# SAMA7G54_DDR3L.net
KiCad netlist of a schematic drawn in Altium Designer
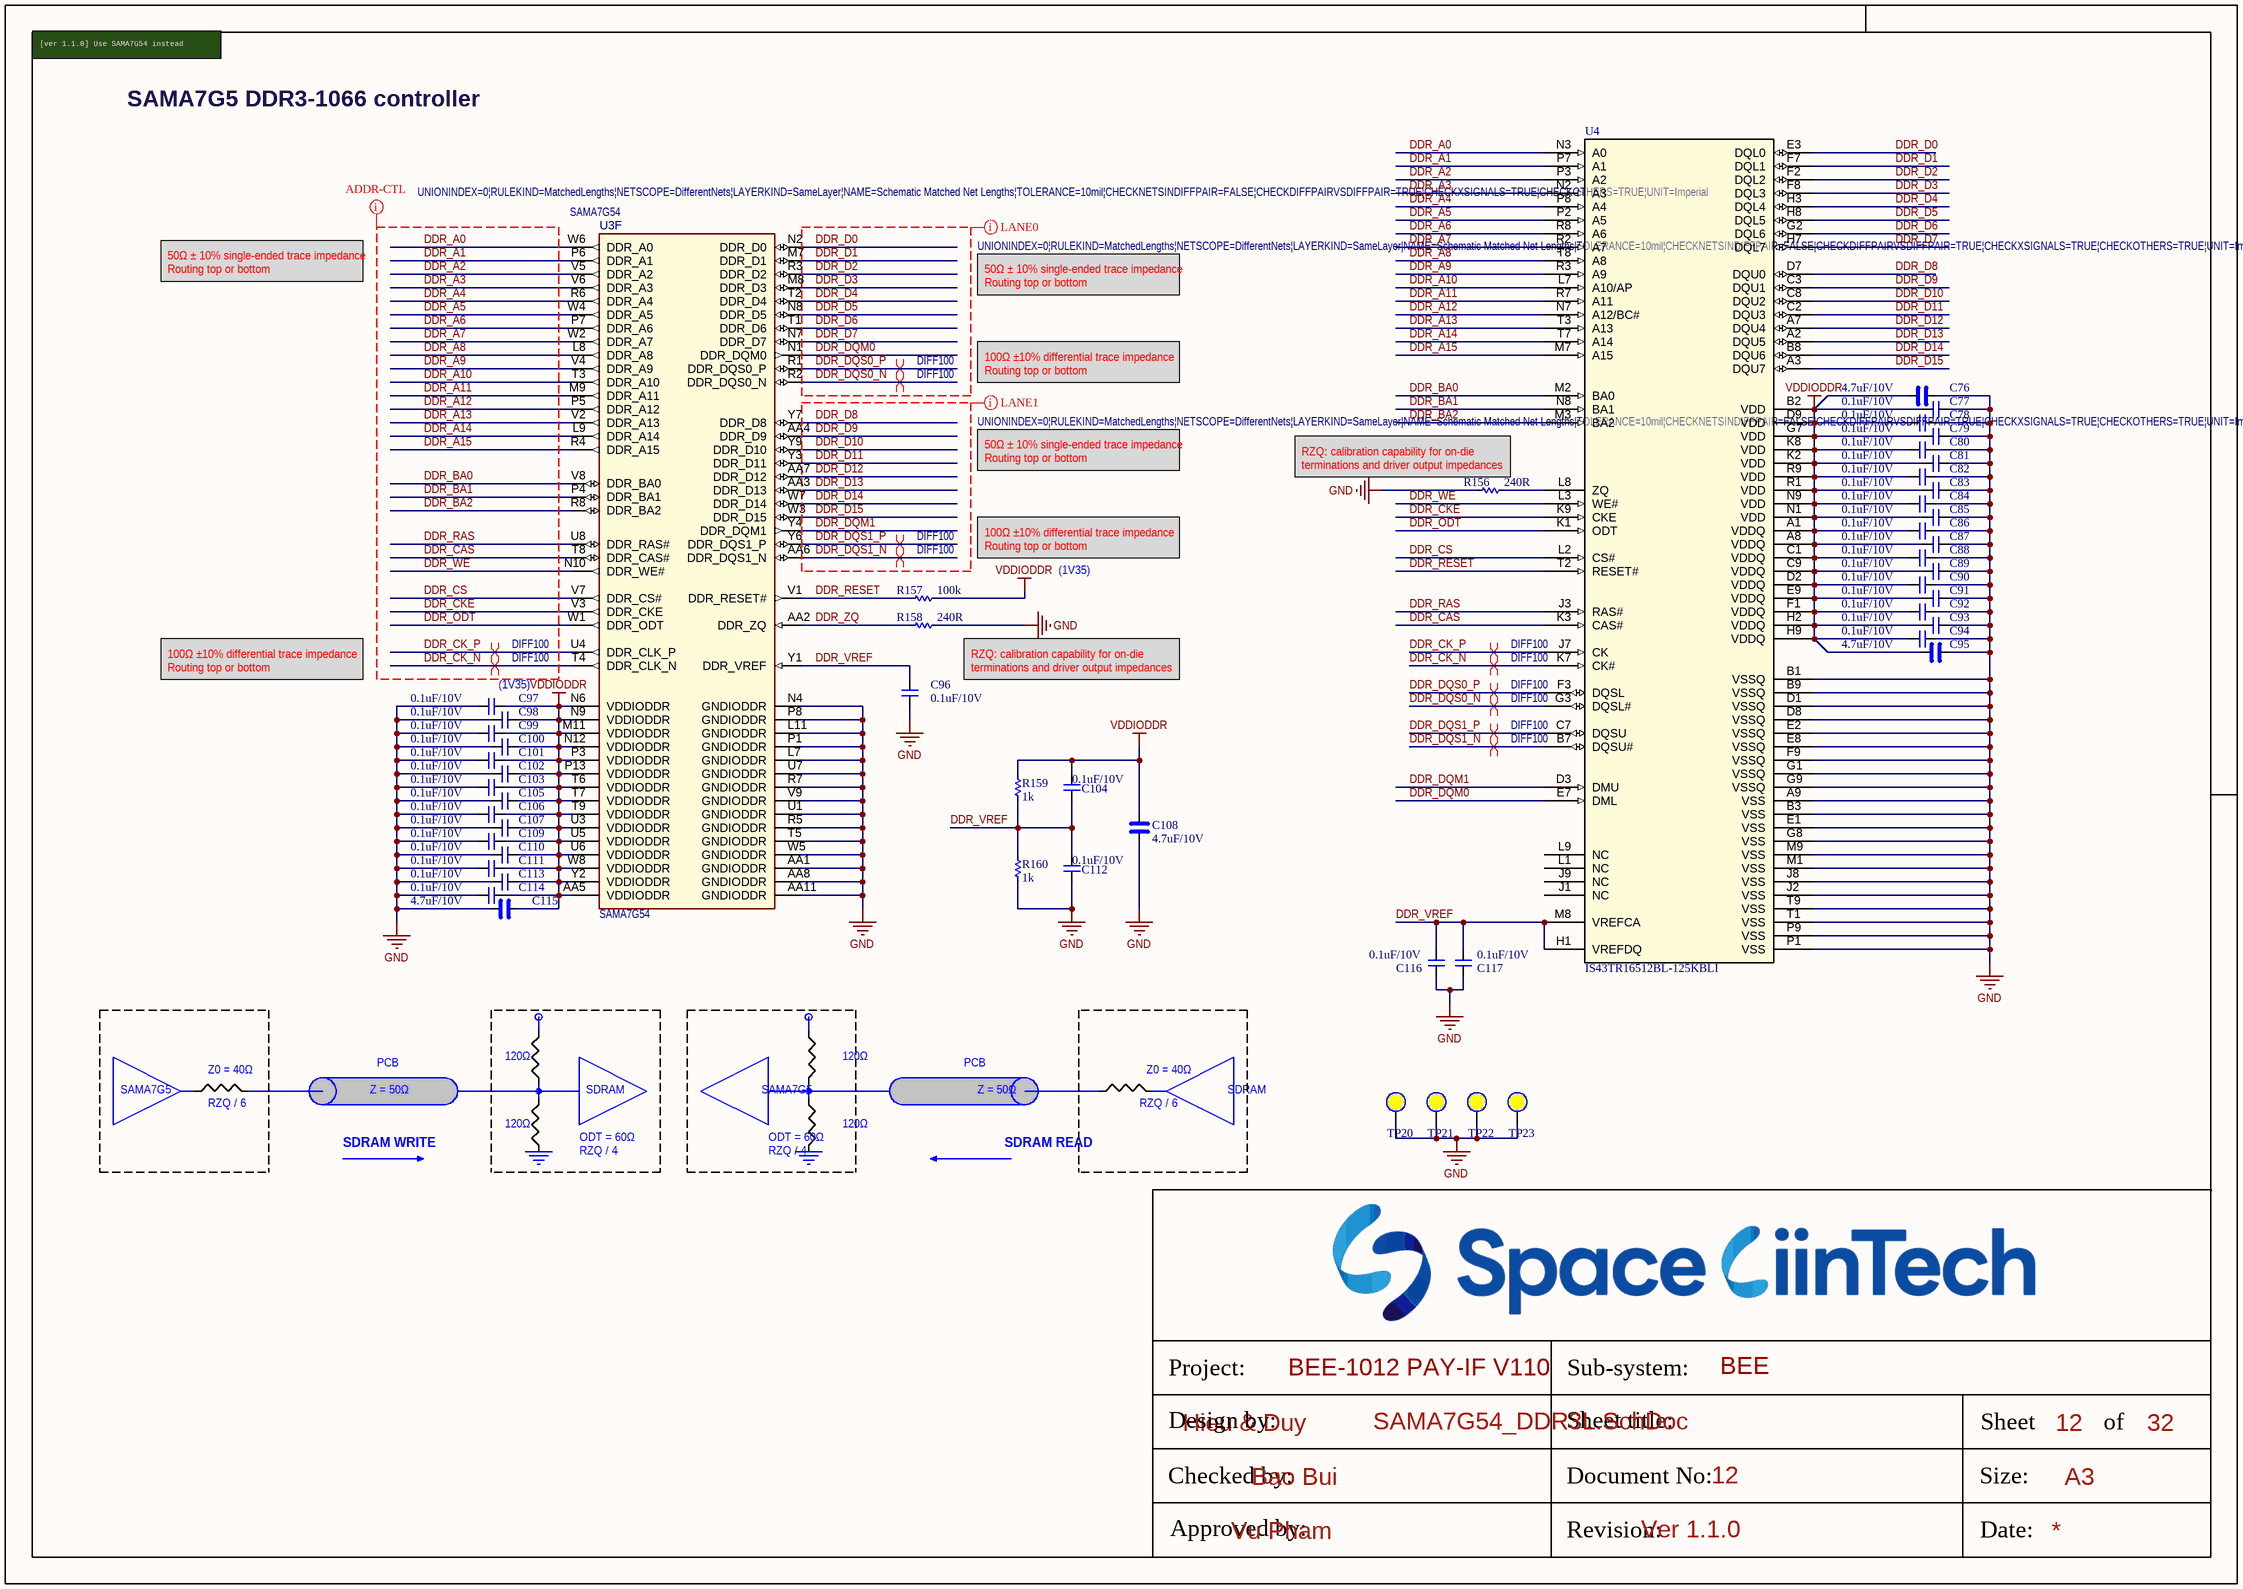
[diagram p0: SAMA7G54_DDR3L.SchDoc]

(export (version "E")
  (design (tool "Eeschema 10.0.6"))
  (components
    (comp (ref "C76")
      (value "4.7uF/10V")
      (footprint "CAP_C_1005X50_L")
      (description "CAP")
      (libsource (lib "LABLIB") (part "_CAP_C_High_2"))
    )
    (comp (ref "C77")
      (value "0.1uF/10V")
      (footprint "CAP_C_0603x30")
      (description "CAP")
      (libsource (lib "LABLIB") (part "_CAP_C_2"))
    )
    (comp (ref "C78")
      (value "0.1uF/10V")
      (footprint "CAP_C_0603x30")
      (description "CAP")
      (libsource (lib "LABLIB") (part "_CAP_C_2"))
    )
    (comp (ref "C79")
      (value "0.1uF/10V")
      (footprint "CAP_C_0603x30")
      (description "CAP")
      (libsource (lib "LABLIB") (part "_CAP_C_2"))
    )
    (comp (ref "C80")
      (value "0.1uF/10V")
      (footprint "CAP_C_0603x30")
      (description "CAP")
      (libsource (lib "LABLIB") (part "_CAP_C_2"))
    )
    (comp (ref "C81")
      (value "0.1uF/10V")
      (footprint "CAP_C_0603x30")
      (description "CAP")
      (libsource (lib "LABLIB") (part "_CAP_C_2"))
    )
    (comp (ref "C82")
      (value "0.1uF/10V")
      (footprint "CAP_C_0603x30")
      (description "CAP")
      (libsource (lib "LABLIB") (part "_CAP_C_2"))
    )
    (comp (ref "C83")
      (value "0.1uF/10V")
      (footprint "CAP_C_0603x30")
      (description "CAP")
      (libsource (lib "LABLIB") (part "_CAP_C_2"))
    )
    (comp (ref "C84")
      (value "0.1uF/10V")
      (footprint "CAP_C_0603x30")
      (description "CAP")
      (libsource (lib "LABLIB") (part "_CAP_C_2"))
    )
    (comp (ref "C85")
      (value "0.1uF/10V")
      (footprint "CAP_C_0603x30")
      (description "CAP")
      (libsource (lib "LABLIB") (part "_CAP_C_2"))
    )
    (comp (ref "C86")
      (value "0.1uF/10V")
      (footprint "CAP_C_0603x30")
      (description "CAP")
      (libsource (lib "LABLIB") (part "_CAP_C_2"))
    )
    (comp (ref "C87")
      (value "0.1uF/10V")
      (footprint "CAP_C_0603x30")
      (description "CAP")
      (libsource (lib "LABLIB") (part "_CAP_C_2"))
    )
    (comp (ref "C88")
      (value "0.1uF/10V")
      (footprint "CAP_C_0603x30")
      (description "CAP")
      (libsource (lib "LABLIB") (part "_CAP_C_2"))
    )
    (comp (ref "C89")
      (value "0.1uF/10V")
      (footprint "CAP_C_0603x30")
      (description "CAP")
      (libsource (lib "LABLIB") (part "_CAP_C_2"))
    )
    (comp (ref "C90")
      (value "0.1uF/10V")
      (footprint "CAP_C_0603x30")
      (description "CAP")
      (libsource (lib "LABLIB") (part "_CAP_C_2"))
    )
    (comp (ref "C91")
      (value "0.1uF/10V")
      (footprint "CAP_C_0603x30")
      (description "CAP")
      (libsource (lib "LABLIB") (part "_CAP_C_2"))
    )
    (comp (ref "C92")
      (value "0.1uF/10V")
      (footprint "CAP_C_0603x30")
      (description "CAP")
      (libsource (lib "LABLIB") (part "_CAP_C_2"))
    )
    (comp (ref "C93")
      (value "0.1uF/10V")
      (footprint "CAP_C_0603x30")
      (description "CAP")
      (libsource (lib "LABLIB") (part "_CAP_C_2"))
    )
    (comp (ref "C94")
      (value "0.1uF/10V")
      (footprint "CAP_C_0603x30")
      (description "CAP")
      (libsource (lib "LABLIB") (part "_CAP_C_2"))
    )
    (comp (ref "C95")
      (value "4.7uF/10V")
      (footprint "CAP_C_1005X50_L")
      (description "CAP")
      (libsource (lib "LABLIB") (part "_CAP_C_High_2"))
    )
    (comp (ref "C96")
      (value "0.1uF/10V")
      (footprint "CAP_C_0603x30")
      (description "CAP")
      (libsource (lib "LABLIB") (part "_CAP_C_2"))
    )
    (comp (ref "C97")
      (value "0.1uF/10V")
      (footprint "CAP_C_0603x30")
      (description "CAP")
      (libsource (lib "LABLIB") (part "_CAP_C_2"))
    )
    (comp (ref "C98")
      (value "0.1uF/10V")
      (footprint "CAP_C_0603x30")
      (description "CAP")
      (libsource (lib "LABLIB") (part "_CAP_C_2"))
    )
    (comp (ref "C99")
      (value "0.1uF/10V")
      (footprint "CAP_C_0603x30")
      (description "CAP")
      (libsource (lib "LABLIB") (part "_CAP_C_2"))
    )
    (comp (ref "C100")
      (value "0.1uF/10V")
      (footprint "CAP_C_0603x30")
      (description "CAP")
      (libsource (lib "LABLIB") (part "_CAP_C_2"))
    )
    (comp (ref "C101")
      (value "0.1uF/10V")
      (footprint "CAP_C_0603x30")
      (description "CAP")
      (libsource (lib "LABLIB") (part "_CAP_C_2"))
    )
    (comp (ref "C102")
      (value "0.1uF/10V")
      (footprint "CAP_C_0603x30")
      (description "CAP")
      (libsource (lib "LABLIB") (part "_CAP_C_2"))
    )
    (comp (ref "C103")
      (value "0.1uF/10V")
      (footprint "CAP_C_0603x30")
      (description "CAP")
      (libsource (lib "LABLIB") (part "_CAP_C_2"))
    )
    (comp (ref "C104")
      (value "0.1uF/10V")
      (footprint "CAP_C_0603x30")
      (description "CAP")
      (libsource (lib "LABLIB") (part "_CAP_C_2"))
    )
    (comp (ref "C105")
      (value "0.1uF/10V")
      (footprint "CAP_C_0603x30")
      (description "CAP")
      (libsource (lib "LABLIB") (part "_CAP_C_2"))
    )
    (comp (ref "C106")
      (value "0.1uF/10V")
      (footprint "CAP_C_0603x30")
      (description "CAP")
      (libsource (lib "LABLIB") (part "_CAP_C_2"))
    )
    (comp (ref "C107")
      (value "0.1uF/10V")
      (footprint "CAP_C_0603x30")
      (description "CAP")
      (libsource (lib "LABLIB") (part "_CAP_C_2"))
    )
    (comp (ref "C108")
      (value "4.7uF/10V")
      (footprint "CAP_C_1005X50_L")
      (description "CAP")
      (libsource (lib "LABLIB") (part "_CAP_C_High_2"))
    )
    (comp (ref "C109")
      (value "0.1uF/10V")
      (footprint "CAP_C_0603x30")
      (description "CAP")
      (libsource (lib "LABLIB") (part "_CAP_C_2"))
    )
    (comp (ref "C110")
      (value "0.1uF/10V")
      (footprint "CAP_C_0603x30")
      (description "CAP")
      (libsource (lib "LABLIB") (part "_CAP_C_2"))
    )
    (comp (ref "C111")
      (value "0.1uF/10V")
      (footprint "CAP_C_0603x30")
      (description "CAP")
      (libsource (lib "LABLIB") (part "_CAP_C_2"))
    )
    (comp (ref "C112")
      (value "0.1uF/10V")
      (footprint "CAP_C_0603x30")
      (description "CAP")
      (libsource (lib "LABLIB") (part "_CAP_C_2"))
    )
    (comp (ref "C113")
      (value "0.1uF/10V")
      (footprint "CAP_C_0603x30")
      (description "CAP")
      (libsource (lib "LABLIB") (part "_CAP_C_2"))
    )
    (comp (ref "C114")
      (value "0.1uF/10V")
      (footprint "CAP_C_0603x30")
      (description "CAP")
      (libsource (lib "LABLIB") (part "_CAP_C_2"))
    )
    (comp (ref "C115")
      (value "4.7uF/10V")
      (footprint "CAP_C_1005X50_L")
      (description "CAP")
      (libsource (lib "LABLIB") (part "_CAP_C_High_2"))
    )
    (comp (ref "C116")
      (value "0.1uF/10V")
      (footprint "CAP_C_0603x30")
      (description "CAP")
      (libsource (lib "LABLIB") (part "_CAP_C_2"))
    )
    (comp (ref "C117")
      (value "0.1uF/10V")
      (footprint "CAP_C_0603x30")
      (description "CAP")
      (libsource (lib "LABLIB") (part "_CAP_C_2"))
    )
    (comp (ref "R156")
      (value "240R")
      (footprint "RES_C_0603X30")
      (description "RES")
      (libsource (lib "LABLIB") (part "_RES_B_2"))
    )
    (comp (ref "R157")
      (value "100k")
      (footprint "RES_C_0603X30")
      (description "RES")
      (libsource (lib "LABLIB") (part "_RES_B_2"))
    )
    (comp (ref "R158")
      (value "240R")
      (footprint "RES_C_0603X30")
      (description "RES")
      (libsource (lib "LABLIB") (part "_RES_B_2"))
    )
    (comp (ref "R159")
      (value "1k")
      (footprint "RES_C_0603X30")
      (description "RES")
      (libsource (lib "LABLIB") (part "_RES_B_2"))
    )
    (comp (ref "R160")
      (value "1k")
      (footprint "RES_C_0603X30")
      (description "RES")
      (libsource (lib "LABLIB") (part "_RES_B_2"))
    )
    (comp (ref "TP20")
      (value "~")
      (footprint "Testpoint_80_pin0")
      (description "Test Point")
      (libsource (lib "IFBschelib") (part "Test Point"))
    )
    (comp (ref "TP21")
      (value "~")
      (footprint "Testpoint_80_pin0")
      (description "Test Point")
      (libsource (lib "IFBschelib") (part "Test Point"))
    )
    (comp (ref "TP22")
      (value "~")
      (footprint "Testpoint_80_pin0")
      (description "Test Point")
      (libsource (lib "IFBschelib") (part "Test Point"))
    )
    (comp (ref "TP23")
      (value "~")
      (footprint "Testpoint_80_pin0")
      (description "Test Point")
      (libsource (lib "IFBschelib") (part "Test Point"))
    )
    (comp (ref "U3")
      (value "SAMA7G54")
      (footprint "TFBGA-343_14x14 - 2.5mm")
      (description "SAMA7G54 MPU 1000MHz Cortex-A7 TFBGA-343")
      (fields (field (name "ALTIUM_VALUE") "SAMA7G54") (field (name "OWNER") "Ciprian Abramov"))
      (libsource (lib "LABLIB") (part "SAMA7G54"))
    )
    (comp (ref "U4")
      (value "IS43TR16512BL-125KBLI")
      (footprint "TWBGA96_ISI")
      (description "DDR3L")
      (fields (field (name "COPYRIGHT") "Copyright (C) 2025 Ultra Librarian. All rights reserved."))
      (libsource (lib "LABLIB") (part "IC_RAM_IS43TR16512BL-125KBLI"))
    )
  )
  (nets
    (net (code "1") (name "/DDR_A0") (class "Default")
      (node (ref "U3") (pin "W6") (pinfunction "DDR_A0_W6") (pintype "output"))
      (node (ref "U4") (pin "N3") (pinfunction "A0_N3") (pintype "input"))
    )
    (net (code "2") (name "/DDR_A1") (class "Default")
      (node (ref "U3") (pin "P6") (pinfunction "DDR_A1_P6") (pintype "output"))
      (node (ref "U4") (pin "P7") (pinfunction "A1_P7") (pintype "input"))
    )
    (net (code "3") (name "/DDR_A2") (class "Default")
      (node (ref "U3") (pin "V5") (pinfunction "DDR_A2_V5") (pintype "output"))
      (node (ref "U4") (pin "P3") (pinfunction "A2_P3") (pintype "input"))
    )
    (net (code "4") (name "/DDR_A3") (class "Default")
      (node (ref "U3") (pin "V6") (pinfunction "DDR_A3_V6") (pintype "output"))
      (node (ref "U4") (pin "N2") (pinfunction "A3_N2") (pintype "input"))
    )
    (net (code "5") (name "/DDR_A4") (class "Default")
      (node (ref "U3") (pin "R6") (pinfunction "DDR_A4_R6") (pintype "output"))
      (node (ref "U4") (pin "P8") (pinfunction "A4_P8") (pintype "input"))
    )
    (net (code "6") (name "/DDR_A5") (class "Default")
      (node (ref "U3") (pin "W4") (pinfunction "DDR_A5_W4") (pintype "output"))
      (node (ref "U4") (pin "P2") (pinfunction "A5_P2") (pintype "input"))
    )
    (net (code "7") (name "/DDR_A6") (class "Default")
      (node (ref "U3") (pin "P7") (pinfunction "DDR_A6_P7") (pintype "output"))
      (node (ref "U4") (pin "R8") (pinfunction "A6_R8") (pintype "input"))
    )
    (net (code "8") (name "/DDR_A7") (class "Default")
      (node (ref "U3") (pin "W2") (pinfunction "DDR_A7_W2") (pintype "output"))
      (node (ref "U4") (pin "R2") (pinfunction "A7_R2") (pintype "input"))
    )
    (net (code "9") (name "/DDR_A8") (class "Default")
      (node (ref "U3") (pin "L8") (pinfunction "DDR_A8_L8") (pintype "output"))
      (node (ref "U4") (pin "T8") (pinfunction "A8_T8") (pintype "input"))
    )
    (net (code "10") (name "/DDR_A9") (class "Default")
      (node (ref "U3") (pin "V4") (pinfunction "DDR_A9_V4") (pintype "output"))
      (node (ref "U4") (pin "R3") (pinfunction "A9_R3") (pintype "input"))
    )
    (net (code "11") (name "/DDR_A10") (class "Default")
      (node (ref "U3") (pin "T3") (pinfunction "DDR_A10_T3") (pintype "output"))
      (node (ref "U4") (pin "L7") (pinfunction "A10/AP_L7") (pintype "input"))
    )
    (net (code "12") (name "/DDR_A11") (class "Default")
      (node (ref "U3") (pin "M9") (pinfunction "DDR_A11_M9") (pintype "output"))
      (node (ref "U4") (pin "R7") (pinfunction "A11_R7") (pintype "input"))
    )
    (net (code "13") (name "/DDR_A12") (class "Default")
      (node (ref "U3") (pin "P5") (pinfunction "DDR_A12_P5") (pintype "output"))
      (node (ref "U4") (pin "N7") (pinfunction "A12/BC#_N7") (pintype "input"))
    )
    (net (code "14") (name "/DDR_A13") (class "Default")
      (node (ref "U3") (pin "V2") (pinfunction "DDR_A13_V2") (pintype "output"))
      (node (ref "U4") (pin "T3") (pinfunction "A13_T3") (pintype "input"))
    )
    (net (code "15") (name "/DDR_A14") (class "Default")
      (node (ref "U3") (pin "L9") (pinfunction "DDR_A14_L9") (pintype "output"))
      (node (ref "U4") (pin "T7") (pinfunction "A14_T7") (pintype "input"))
    )
    (net (code "16") (name "/DDR_A15") (class "Default")
      (node (ref "U3") (pin "R4") (pinfunction "DDR_A15_R4") (pintype "output"))
      (node (ref "U4") (pin "M7") (pinfunction "A15_M7") (pintype "input"))
    )
    (net (code "17") (name "/DDR_BA0") (class "Default")
      (node (ref "U3") (pin "V8") (pinfunction "DDR_BA0_V8") (pintype "bidirectional"))
      (node (ref "U4") (pin "M2") (pinfunction "BA0_M2") (pintype "input"))
    )
    (net (code "18") (name "/DDR_BA1") (class "Default")
      (node (ref "U3") (pin "P4") (pinfunction "DDR_BA1_P4") (pintype "bidirectional"))
      (node (ref "U4") (pin "N8") (pinfunction "BA1_N8") (pintype "input"))
    )
    (net (code "19") (name "/DDR_BA2") (class "Default")
      (node (ref "U3") (pin "R8") (pinfunction "DDR_BA2_R8") (pintype "bidirectional"))
      (node (ref "U4") (pin "M3") (pinfunction "BA2_M3") (pintype "input"))
    )
    (net (code "20") (name "/DDR_CAS") (class "Default")
      (node (ref "U3") (pin "T8") (pinfunction "DDR_CAS#_T8") (pintype "bidirectional"))
      (node (ref "U4") (pin "K3") (pinfunction "CAS#_K3") (pintype "input"))
    )
    (net (code "21") (name "/DDR_CKE") (class "Default")
      (node (ref "U3") (pin "V3") (pinfunction "DDR_CKE_V3") (pintype "output"))
      (node (ref "U4") (pin "K9") (pinfunction "CKE_K9") (pintype "input"))
    )
    (net (code "22") (name "/DDR_CK_N") (class "Default")
      (node (ref "U3") (pin "T4") (pinfunction "DDR_CLK_N_T4") (pintype "output"))
      (node (ref "U4") (pin "K7") (pinfunction "CK#_K7") (pintype "input"))
    )
    (net (code "23") (name "/DDR_CK_P") (class "Default")
      (node (ref "U3") (pin "U4") (pinfunction "DDR_CLK_P_U4") (pintype "output"))
      (node (ref "U4") (pin "J7") (pinfunction "CK_J7") (pintype "input"))
    )
    (net (code "24") (name "/DDR_CS") (class "Default")
      (node (ref "U3") (pin "V7") (pinfunction "DDR_CS#_V7") (pintype "output"))
      (node (ref "U4") (pin "L2") (pinfunction "CS#_L2") (pintype "input"))
    )
    (net (code "25") (name "/DDR_D0") (class "Default")
      (node (ref "U3") (pin "N2") (pinfunction "DDR_D0_N2") (pintype "bidirectional"))
      (node (ref "U4") (pin "E3") (pinfunction "DQL0_E3") (pintype "bidirectional"))
    )
    (net (code "26") (name "/DDR_D1") (class "Default")
      (node (ref "U3") (pin "M7") (pinfunction "DDR_D1_M7") (pintype "bidirectional"))
      (node (ref "U4") (pin "F7") (pinfunction "DQL1_F7") (pintype "bidirectional"))
    )
    (net (code "27") (name "/DDR_D2") (class "Default")
      (node (ref "U3") (pin "R3") (pinfunction "DDR_D2_R3") (pintype "bidirectional"))
      (node (ref "U4") (pin "F2") (pinfunction "DQL2_F2") (pintype "bidirectional"))
    )
    (net (code "28") (name "/DDR_D3") (class "Default")
      (node (ref "U3") (pin "M8") (pinfunction "DDR_D3_M8") (pintype "bidirectional"))
      (node (ref "U4") (pin "F8") (pinfunction "DQL3_F8") (pintype "bidirectional"))
    )
    (net (code "29") (name "/DDR_D4") (class "Default")
      (node (ref "U3") (pin "T2") (pinfunction "DDR_D4_T2") (pintype "bidirectional"))
      (node (ref "U4") (pin "H3") (pinfunction "DQL4_H3") (pintype "bidirectional"))
    )
    (net (code "30") (name "/DDR_D5") (class "Default")
      (node (ref "U3") (pin "N8") (pinfunction "DDR_D5_N8") (pintype "bidirectional"))
      (node (ref "U4") (pin "H8") (pinfunction "DQL5_H8") (pintype "bidirectional"))
    )
    (net (code "31") (name "/DDR_D6") (class "Default")
      (node (ref "U3") (pin "T1") (pinfunction "DDR_D6_T1") (pintype "bidirectional"))
      (node (ref "U4") (pin "G2") (pinfunction "DQL6_G2") (pintype "bidirectional"))
    )
    (net (code "32") (name "/DDR_D7") (class "Default")
      (node (ref "U3") (pin "N7") (pinfunction "DDR_D7_N7") (pintype "bidirectional"))
      (node (ref "U4") (pin "H7") (pinfunction "DQL7_H7") (pintype "bidirectional"))
    )
    (net (code "33") (name "/DDR_D8") (class "Default")
      (node (ref "U3") (pin "Y7") (pinfunction "DDR_D8_Y7") (pintype "bidirectional"))
      (node (ref "U4") (pin "D7") (pinfunction "DQU0_D7") (pintype "bidirectional"))
    )
    (net (code "34") (name "/DDR_D9") (class "Default")
      (node (ref "U3") (pin "AA4") (pinfunction "DDR_D9_AA4") (pintype "bidirectional"))
      (node (ref "U4") (pin "C3") (pinfunction "DQU1_C3") (pintype "bidirectional"))
    )
    (net (code "35") (name "/DDR_D10") (class "Default")
      (node (ref "U3") (pin "Y9") (pinfunction "DDR_D10_Y9") (pintype "bidirectional"))
      (node (ref "U4") (pin "C8") (pinfunction "DQU2_C8") (pintype "bidirectional"))
    )
    (net (code "36") (name "/DDR_D11") (class "Default")
      (node (ref "U3") (pin "Y3") (pinfunction "DDR_D11_Y3") (pintype "bidirectional"))
      (node (ref "U4") (pin "C2") (pinfunction "DQU3_C2") (pintype "bidirectional"))
    )
    (net (code "37") (name "/DDR_D12") (class "Default")
      (node (ref "U3") (pin "AA7") (pinfunction "DDR_D12_AA7") (pintype "bidirectional"))
      (node (ref "U4") (pin "A7") (pinfunction "DQU4_A7") (pintype "bidirectional"))
    )
    (net (code "38") (name "/DDR_D13") (class "Default")
      (node (ref "U3") (pin "AA3") (pinfunction "DDR_D13_AA3") (pintype "bidirectional"))
      (node (ref "U4") (pin "A2") (pinfunction "DQU5_A2") (pintype "bidirectional"))
    )
    (net (code "39") (name "/DDR_D14") (class "Default")
      (node (ref "U3") (pin "W7") (pinfunction "DDR_D14_W7") (pintype "bidirectional"))
      (node (ref "U4") (pin "B8") (pinfunction "DQU6_B8") (pintype "bidirectional"))
    )
    (net (code "40") (name "/DDR_D15") (class "Default")
      (node (ref "U3") (pin "W3") (pinfunction "DDR_D15_W3") (pintype "bidirectional"))
      (node (ref "U4") (pin "A3") (pinfunction "DQU7_A3") (pintype "bidirectional"))
    )
    (net (code "41") (name "/DDR_DQM0") (class "Default")
      (node (ref "U3") (pin "N1") (pinfunction "DDR_DQM0_N1") (pintype "output"))
      (node (ref "U4") (pin "E7") (pinfunction "DML_E7") (pintype "input"))
    )
    (net (code "42") (name "/DDR_DQM1") (class "Default")
      (node (ref "U3") (pin "Y4") (pinfunction "DDR_DQM1_Y4") (pintype "output"))
      (node (ref "U4") (pin "D3") (pinfunction "DMU_D3") (pintype "input"))
    )
    (net (code "43") (name "/DDR_DQS0_N") (class "Default")
      (node (ref "U3") (pin "R2") (pinfunction "DDR_DQS0_N_R2") (pintype "bidirectional"))
      (node (ref "U4") (pin "G3") (pinfunction "DQSL#_G3") (pintype "bidirectional"))
    )
    (net (code "44") (name "/DDR_DQS0_P") (class "Default")
      (node (ref "U3") (pin "R1") (pinfunction "DDR_DQS0_P_R1") (pintype "bidirectional"))
      (node (ref "U4") (pin "F3") (pinfunction "DQSL_F3") (pintype "bidirectional"))
    )
    (net (code "45") (name "/DDR_DQS1_N") (class "Default")
      (node (ref "U3") (pin "AA6") (pinfunction "DDR_DQS1_N_AA6") (pintype "bidirectional"))
      (node (ref "U4") (pin "B7") (pinfunction "DQSU#_B7") (pintype "bidirectional"))
    )
    (net (code "46") (name "/DDR_DQS1_P") (class "Default")
      (node (ref "U3") (pin "Y6") (pinfunction "DDR_DQS1_P_Y6") (pintype "bidirectional"))
      (node (ref "U4") (pin "C7") (pinfunction "DQSU_C7") (pintype "bidirectional"))
    )
    (net (code "47") (name "/DDR_ODT") (class "Default")
      (node (ref "U3") (pin "W1") (pinfunction "DDR_ODT_W1") (pintype "output"))
      (node (ref "U4") (pin "K1") (pinfunction "ODT_K1") (pintype "input"))
    )
    (net (code "48") (name "/DDR_RAS") (class "Default")
      (node (ref "U3") (pin "U8") (pinfunction "DDR_RAS#_U8") (pintype "bidirectional"))
      (node (ref "U4") (pin "J3") (pinfunction "RAS#_J3") (pintype "input"))
    )
    (net (code "49") (name "/DDR_RESET") (class "Default")
      (node (ref "R157") (pin "2") (pinfunction "2_2") (pintype "passive"))
      (node (ref "U3") (pin "V1") (pinfunction "DDR_RESET#_V1") (pintype "output"))
      (node (ref "U4") (pin "T2") (pinfunction "RESET#_T2") (pintype "input"))
    )
    (net (code "50") (name "/DDR_VREF") (class "Default")
      (node (ref "C104") (pin "2") (pinfunction "2_2") (pintype "passive"))
      (node (ref "C112") (pin "1") (pinfunction "1_1") (pintype "passive"))
      (node (ref "C116") (pin "1") (pinfunction "1_1") (pintype "passive"))
      (node (ref "C117") (pin "1") (pinfunction "1_1") (pintype "passive"))
      (node (ref "C96") (pin "1") (pinfunction "1_1") (pintype "passive"))
      (node (ref "R159") (pin "2") (pinfunction "2_2") (pintype "passive"))
      (node (ref "R160") (pin "1") (pinfunction "1_1") (pintype "passive"))
      (node (ref "U3") (pin "Y1") (pinfunction "DDR_VREF_Y1") (pintype "input"))
      (node (ref "U4") (pin "H1") (pinfunction "VREFDQ_H1") (pintype "power_in"))
      (node (ref "U4") (pin "M8") (pinfunction "VREFCA_M8") (pintype "power_in"))
    )
    (net (code "51") (name "/DDR_WE") (class "Default")
      (node (ref "U3") (pin "N10") (pinfunction "DDR_WE#_N10") (pintype "output"))
      (node (ref "U4") (pin "L3") (pinfunction "WE#_L3") (pintype "input"))
    )
    (net (code "52") (name "/DDR_ZQ") (class "Default")
      (node (ref "R158") (pin "2") (pinfunction "2_2") (pintype "passive"))
      (node (ref "U3") (pin "AA2") (pinfunction "DDR_ZQ_AA2") (pintype "input"))
    )
    (net (code "53") (name "GND") (class "Default")
      (node (ref "C100") (pin "2") (pinfunction "2_2") (pintype "passive"))
      (node (ref "C101") (pin "2") (pinfunction "2_2") (pintype "passive"))
      (node (ref "C102") (pin "2") (pinfunction "2_2") (pintype "passive"))
      (node (ref "C103") (pin "2") (pinfunction "2_2") (pintype "passive"))
      (node (ref "C105") (pin "2") (pinfunction "2_2") (pintype "passive"))
      (node (ref "C106") (pin "2") (pinfunction "2_2") (pintype "passive"))
      (node (ref "C107") (pin "2") (pinfunction "2_2") (pintype "passive"))
      (node (ref "C108") (pin "2") (pinfunction "2_2") (pintype "passive"))
      (node (ref "C109") (pin "2") (pinfunction "2_2") (pintype "passive"))
      (node (ref "C110") (pin "2") (pinfunction "2_2") (pintype "passive"))
      (node (ref "C111") (pin "2") (pinfunction "2_2") (pintype "passive"))
      (node (ref "C112") (pin "2") (pinfunction "2_2") (pintype "passive"))
      (node (ref "C113") (pin "2") (pinfunction "2_2") (pintype "passive"))
      (node (ref "C114") (pin "2") (pinfunction "2_2") (pintype "passive"))
      (node (ref "C115") (pin "2") (pinfunction "2_2") (pintype "passive"))
      (node (ref "C116") (pin "2") (pinfunction "2_2") (pintype "passive"))
      (node (ref "C117") (pin "2") (pinfunction "2_2") (pintype "passive"))
      (node (ref "C76") (pin "1") (pinfunction "1_1") (pintype "passive"))
      (node (ref "C77") (pin "1") (pinfunction "1_1") (pintype "passive"))
      (node (ref "C78") (pin "1") (pinfunction "1_1") (pintype "passive"))
      (node (ref "C79") (pin "1") (pinfunction "1_1") (pintype "passive"))
      (node (ref "C80") (pin "1") (pinfunction "1_1") (pintype "passive"))
      (node (ref "C81") (pin "1") (pinfunction "1_1") (pintype "passive"))
      (node (ref "C82") (pin "1") (pinfunction "1_1") (pintype "passive"))
      (node (ref "C83") (pin "1") (pinfunction "1_1") (pintype "passive"))
      (node (ref "C84") (pin "1") (pinfunction "1_1") (pintype "passive"))
      (node (ref "C85") (pin "1") (pinfunction "1_1") (pintype "passive"))
      (node (ref "C86") (pin "1") (pinfunction "1_1") (pintype "passive"))
      (node (ref "C87") (pin "1") (pinfunction "1_1") (pintype "passive"))
      (node (ref "C88") (pin "1") (pinfunction "1_1") (pintype "passive"))
      (node (ref "C89") (pin "1") (pinfunction "1_1") (pintype "passive"))
      (node (ref "C90") (pin "1") (pinfunction "1_1") (pintype "passive"))
      (node (ref "C91") (pin "1") (pinfunction "1_1") (pintype "passive"))
      (node (ref "C92") (pin "1") (pinfunction "1_1") (pintype "passive"))
      (node (ref "C93") (pin "1") (pinfunction "1_1") (pintype "passive"))
      (node (ref "C94") (pin "1") (pinfunction "1_1") (pintype "passive"))
      (node (ref "C95") (pin "1") (pinfunction "1_1") (pintype "passive"))
      (node (ref "C96") (pin "2") (pinfunction "2_2") (pintype "passive"))
      (node (ref "C97") (pin "2") (pinfunction "2_2") (pintype "passive"))
      (node (ref "C98") (pin "2") (pinfunction "2_2") (pintype "passive"))
      (node (ref "C99") (pin "2") (pinfunction "2_2") (pintype "passive"))
      (node (ref "R156") (pin "2") (pinfunction "2_2") (pintype "passive"))
      (node (ref "R158") (pin "1") (pinfunction "1_1") (pintype "passive"))
      (node (ref "R160") (pin "2") (pinfunction "2_2") (pintype "passive"))
      (node (ref "TP20") (pin "0") (pinfunction "0_0") (pintype "passive"))
      (node (ref "TP21") (pin "0") (pinfunction "0_0") (pintype "passive"))
      (node (ref "TP22") (pin "0") (pinfunction "0_0") (pintype "passive"))
      (node (ref "TP23") (pin "0") (pinfunction "0_0") (pintype "passive"))
      (node (ref "U3") (pin "AA1") (pinfunction "GNDIODDR_AA1") (pintype "power_in"))
      (node (ref "U3") (pin "AA11") (pinfunction "GNDIODDR_AA11") (pintype "power_in"))
      (node (ref "U3") (pin "AA8") (pinfunction "GNDIODDR_AA8") (pintype "power_in"))
      (node (ref "U3") (pin "L11") (pinfunction "GNDIODDR_L11") (pintype "power_in"))
      (node (ref "U3") (pin "L7") (pinfunction "GNDIODDR_L7") (pintype "power_in"))
      (node (ref "U3") (pin "N4") (pinfunction "GNDIODDR_N4") (pintype "power_in"))
      (node (ref "U3") (pin "P1") (pinfunction "GNDIODDR_P1") (pintype "power_in"))
      (node (ref "U3") (pin "P8") (pinfunction "GNDIODDR_P8") (pintype "power_in"))
      (node (ref "U3") (pin "R5") (pinfunction "GNDIODDR_R5") (pintype "power_in"))
      (node (ref "U3") (pin "R7") (pinfunction "GNDIODDR_R7") (pintype "power_in"))
      (node (ref "U3") (pin "T5") (pinfunction "GNDIODDR_T5") (pintype "power_in"))
      (node (ref "U3") (pin "U1") (pinfunction "GNDIODDR_U1") (pintype "power_in"))
      (node (ref "U3") (pin "U7") (pinfunction "GNDIODDR_U7") (pintype "power_in"))
      (node (ref "U3") (pin "V9") (pinfunction "GNDIODDR_V9") (pintype "power_in"))
      (node (ref "U3") (pin "W5") (pinfunction "GNDIODDR_W5") (pintype "power_in"))
      (node (ref "U4") (pin "A9") (pinfunction "VSS_A9") (pintype "power_in"))
      (node (ref "U4") (pin "B1") (pinfunction "VSSQ_B1") (pintype "power_in"))
      (node (ref "U4") (pin "B3") (pinfunction "VSS_B3") (pintype "power_in"))
      (node (ref "U4") (pin "B9") (pinfunction "VSSQ_B9") (pintype "power_in"))
      (node (ref "U4") (pin "D1") (pinfunction "VSSQ_D1") (pintype "power_in"))
      (node (ref "U4") (pin "D8") (pinfunction "VSSQ_D8") (pintype "power_in"))
      (node (ref "U4") (pin "E1") (pinfunction "VSS_E1") (pintype "power_in"))
      (node (ref "U4") (pin "E2") (pinfunction "VSSQ_E2") (pintype "power_in"))
      (node (ref "U4") (pin "E8") (pinfunction "VSSQ_E8") (pintype "power_in"))
      (node (ref "U4") (pin "F9") (pinfunction "VSSQ_F9") (pintype "power_in"))
      (node (ref "U4") (pin "G1") (pinfunction "VSSQ_G1") (pintype "power_in"))
      (node (ref "U4") (pin "G8") (pinfunction "VSS_G8") (pintype "power_in"))
      (node (ref "U4") (pin "G9") (pinfunction "VSSQ_G9") (pintype "power_in"))
      (node (ref "U4") (pin "J2") (pinfunction "VSS_J2") (pintype "power_in"))
      (node (ref "U4") (pin "J8") (pinfunction "VSS_J8") (pintype "power_in"))
      (node (ref "U4") (pin "M1") (pinfunction "VSS_M1") (pintype "power_in"))
      (node (ref "U4") (pin "M9") (pinfunction "VSS_M9") (pintype "power_in"))
      (node (ref "U4") (pin "P1") (pinfunction "VSS_P1") (pintype "power_in"))
      (node (ref "U4") (pin "P9") (pinfunction "VSS_P9") (pintype "power_in"))
      (node (ref "U4") (pin "T1") (pinfunction "VSS_T1") (pintype "power_in"))
      (node (ref "U4") (pin "T9") (pinfunction "VSS_T9") (pintype "power_in"))
    )
    (net (code "54") (name "Net-(U4-ZQ)") (class "Default")
      (node (ref "R156") (pin "1") (pinfunction "1_1") (pintype "passive"))
      (node (ref "U4") (pin "L8") (pinfunction "ZQ_L8") (pintype "power_in"))
    )
    (net (code "55") (name "VDDIODDR") (class "Default")
      (node (ref "C100") (pin "1") (pinfunction "1_1") (pintype "passive"))
      (node (ref "C101") (pin "1") (pinfunction "1_1") (pintype "passive"))
      (node (ref "C102") (pin "1") (pinfunction "1_1") (pintype "passive"))
      (node (ref "C103") (pin "1") (pinfunction "1_1") (pintype "passive"))
      (node (ref "C104") (pin "1") (pinfunction "1_1") (pintype "passive"))
      (node (ref "C105") (pin "1") (pinfunction "1_1") (pintype "passive"))
      (node (ref "C106") (pin "1") (pinfunction "1_1") (pintype "passive"))
      (node (ref "C107") (pin "1") (pinfunction "1_1") (pintype "passive"))
      (node (ref "C108") (pin "1") (pinfunction "1_1") (pintype "passive"))
      (node (ref "C109") (pin "1") (pinfunction "1_1") (pintype "passive"))
      (node (ref "C110") (pin "1") (pinfunction "1_1") (pintype "passive"))
      (node (ref "C111") (pin "1") (pinfunction "1_1") (pintype "passive"))
      (node (ref "C113") (pin "1") (pinfunction "1_1") (pintype "passive"))
      (node (ref "C114") (pin "1") (pinfunction "1_1") (pintype "passive"))
      (node (ref "C115") (pin "1") (pinfunction "1_1") (pintype "passive"))
      (node (ref "C76") (pin "2") (pinfunction "2_2") (pintype "passive"))
      (node (ref "C77") (pin "2") (pinfunction "2_2") (pintype "passive"))
      (node (ref "C78") (pin "2") (pinfunction "2_2") (pintype "passive"))
      (node (ref "C79") (pin "2") (pinfunction "2_2") (pintype "passive"))
      (node (ref "C80") (pin "2") (pinfunction "2_2") (pintype "passive"))
      (node (ref "C81") (pin "2") (pinfunction "2_2") (pintype "passive"))
      (node (ref "C82") (pin "2") (pinfunction "2_2") (pintype "passive"))
      (node (ref "C83") (pin "2") (pinfunction "2_2") (pintype "passive"))
      (node (ref "C84") (pin "2") (pinfunction "2_2") (pintype "passive"))
      (node (ref "C85") (pin "2") (pinfunction "2_2") (pintype "passive"))
      (node (ref "C86") (pin "2") (pinfunction "2_2") (pintype "passive"))
      (node (ref "C87") (pin "2") (pinfunction "2_2") (pintype "passive"))
      (node (ref "C88") (pin "2") (pinfunction "2_2") (pintype "passive"))
      (node (ref "C89") (pin "2") (pinfunction "2_2") (pintype "passive"))
      (node (ref "C90") (pin "2") (pinfunction "2_2") (pintype "passive"))
      (node (ref "C91") (pin "2") (pinfunction "2_2") (pintype "passive"))
      (node (ref "C92") (pin "2") (pinfunction "2_2") (pintype "passive"))
      (node (ref "C93") (pin "2") (pinfunction "2_2") (pintype "passive"))
      (node (ref "C94") (pin "2") (pinfunction "2_2") (pintype "passive"))
      (node (ref "C95") (pin "2") (pinfunction "2_2") (pintype "passive"))
      (node (ref "C97") (pin "1") (pinfunction "1_1") (pintype "passive"))
      (node (ref "C98") (pin "1") (pinfunction "1_1") (pintype "passive"))
      (node (ref "C99") (pin "1") (pinfunction "1_1") (pintype "passive"))
      (node (ref "R157") (pin "1") (pinfunction "1_1") (pintype "passive"))
      (node (ref "R159") (pin "1") (pinfunction "1_1") (pintype "passive"))
      (node (ref "U3") (pin "AA5") (pinfunction "VDDIODDR_AA5") (pintype "power_in"))
      (node (ref "U3") (pin "M11") (pinfunction "VDDIODDR_M11") (pintype "power_in"))
      (node (ref "U3") (pin "N12") (pinfunction "VDDIODDR_N12") (pintype "power_in"))
      (node (ref "U3") (pin "N6") (pinfunction "VDDIODDR_N6") (pintype "power_in"))
      (node (ref "U3") (pin "N9") (pinfunction "VDDIODDR_N9") (pintype "power_in"))
      (node (ref "U3") (pin "P13") (pinfunction "VDDIODDR_P13") (pintype "power_in"))
      (node (ref "U3") (pin "P3") (pinfunction "VDDIODDR_P3") (pintype "power_in"))
      (node (ref "U3") (pin "T6") (pinfunction "VDDIODDR_T6") (pintype "power_in"))
      (node (ref "U3") (pin "T7") (pinfunction "VDDIODDR_T7") (pintype "power_in"))
      (node (ref "U3") (pin "T9") (pinfunction "VDDIODDR_T9") (pintype "power_in"))
      (node (ref "U3") (pin "U3") (pinfunction "VDDIODDR_U3") (pintype "power_in"))
      (node (ref "U3") (pin "U5") (pinfunction "VDDIODDR_U5") (pintype "power_in"))
      (node (ref "U3") (pin "U6") (pinfunction "VDDIODDR_U6") (pintype "power_in"))
      (node (ref "U3") (pin "W8") (pinfunction "VDDIODDR_W8") (pintype "power_in"))
      (node (ref "U3") (pin "Y2") (pinfunction "VDDIODDR_Y2") (pintype "power_in"))
      (node (ref "U4") (pin "A1") (pinfunction "VDDQ_A1") (pintype "power_in"))
      (node (ref "U4") (pin "A8") (pinfunction "VDDQ_A8") (pintype "power_in"))
      (node (ref "U4") (pin "B2") (pinfunction "VDD_B2") (pintype "power_in"))
      (node (ref "U4") (pin "C1") (pinfunction "VDDQ_C1") (pintype "power_in"))
      (node (ref "U4") (pin "C9") (pinfunction "VDDQ_C9") (pintype "power_in"))
      (node (ref "U4") (pin "D2") (pinfunction "VDDQ_D2") (pintype "power_in"))
      (node (ref "U4") (pin "D9") (pinfunction "VDD_D9") (pintype "power_in"))
      (node (ref "U4") (pin "E9") (pinfunction "VDDQ_E9") (pintype "power_in"))
      (node (ref "U4") (pin "F1") (pinfunction "VDDQ_F1") (pintype "power_in"))
      (node (ref "U4") (pin "G7") (pinfunction "VDD_G7") (pintype "power_in"))
      (node (ref "U4") (pin "H2") (pinfunction "VDDQ_H2") (pintype "power_in"))
      (node (ref "U4") (pin "H9") (pinfunction "VDDQ_H9") (pintype "power_in"))
      (node (ref "U4") (pin "K2") (pinfunction "VDD_K2") (pintype "power_in"))
      (node (ref "U4") (pin "K8") (pinfunction "VDD_K8") (pintype "power_in"))
      (node (ref "U4") (pin "N1") (pinfunction "VDD_N1") (pintype "power_in"))
      (node (ref "U4") (pin "N9") (pinfunction "VDD_N9") (pintype "power_in"))
      (node (ref "U4") (pin "R1") (pinfunction "VDD_R1") (pintype "power_in"))
      (node (ref "U4") (pin "R9") (pinfunction "VDD_R9") (pintype "power_in"))
    )
    (net (code "56") (name "unconnected-(U4-NC-PadJ1)") (class "Default")
      (node (ref "U4") (pin "J1") (pinfunction "NC_J1") (pintype "passive"))
    )
    (net (code "57") (name "unconnected-(U4-NC-PadJ9)") (class "Default")
      (node (ref "U4") (pin "J9") (pinfunction "NC_J9") (pintype "passive"))
    )
    (net (code "58") (name "unconnected-(U4-NC-PadL1)") (class "Default")
      (node (ref "U4") (pin "L1") (pinfunction "NC_L1") (pintype "passive"))
    )
    (net (code "59") (name "unconnected-(U4-NC-PadL9)") (class "Default")
      (node (ref "U4") (pin "L9") (pinfunction "NC_L9") (pintype "passive"))
    )
  )
)
